# hihats.net
KiCad netlist of a schematic drawn in EAGLE
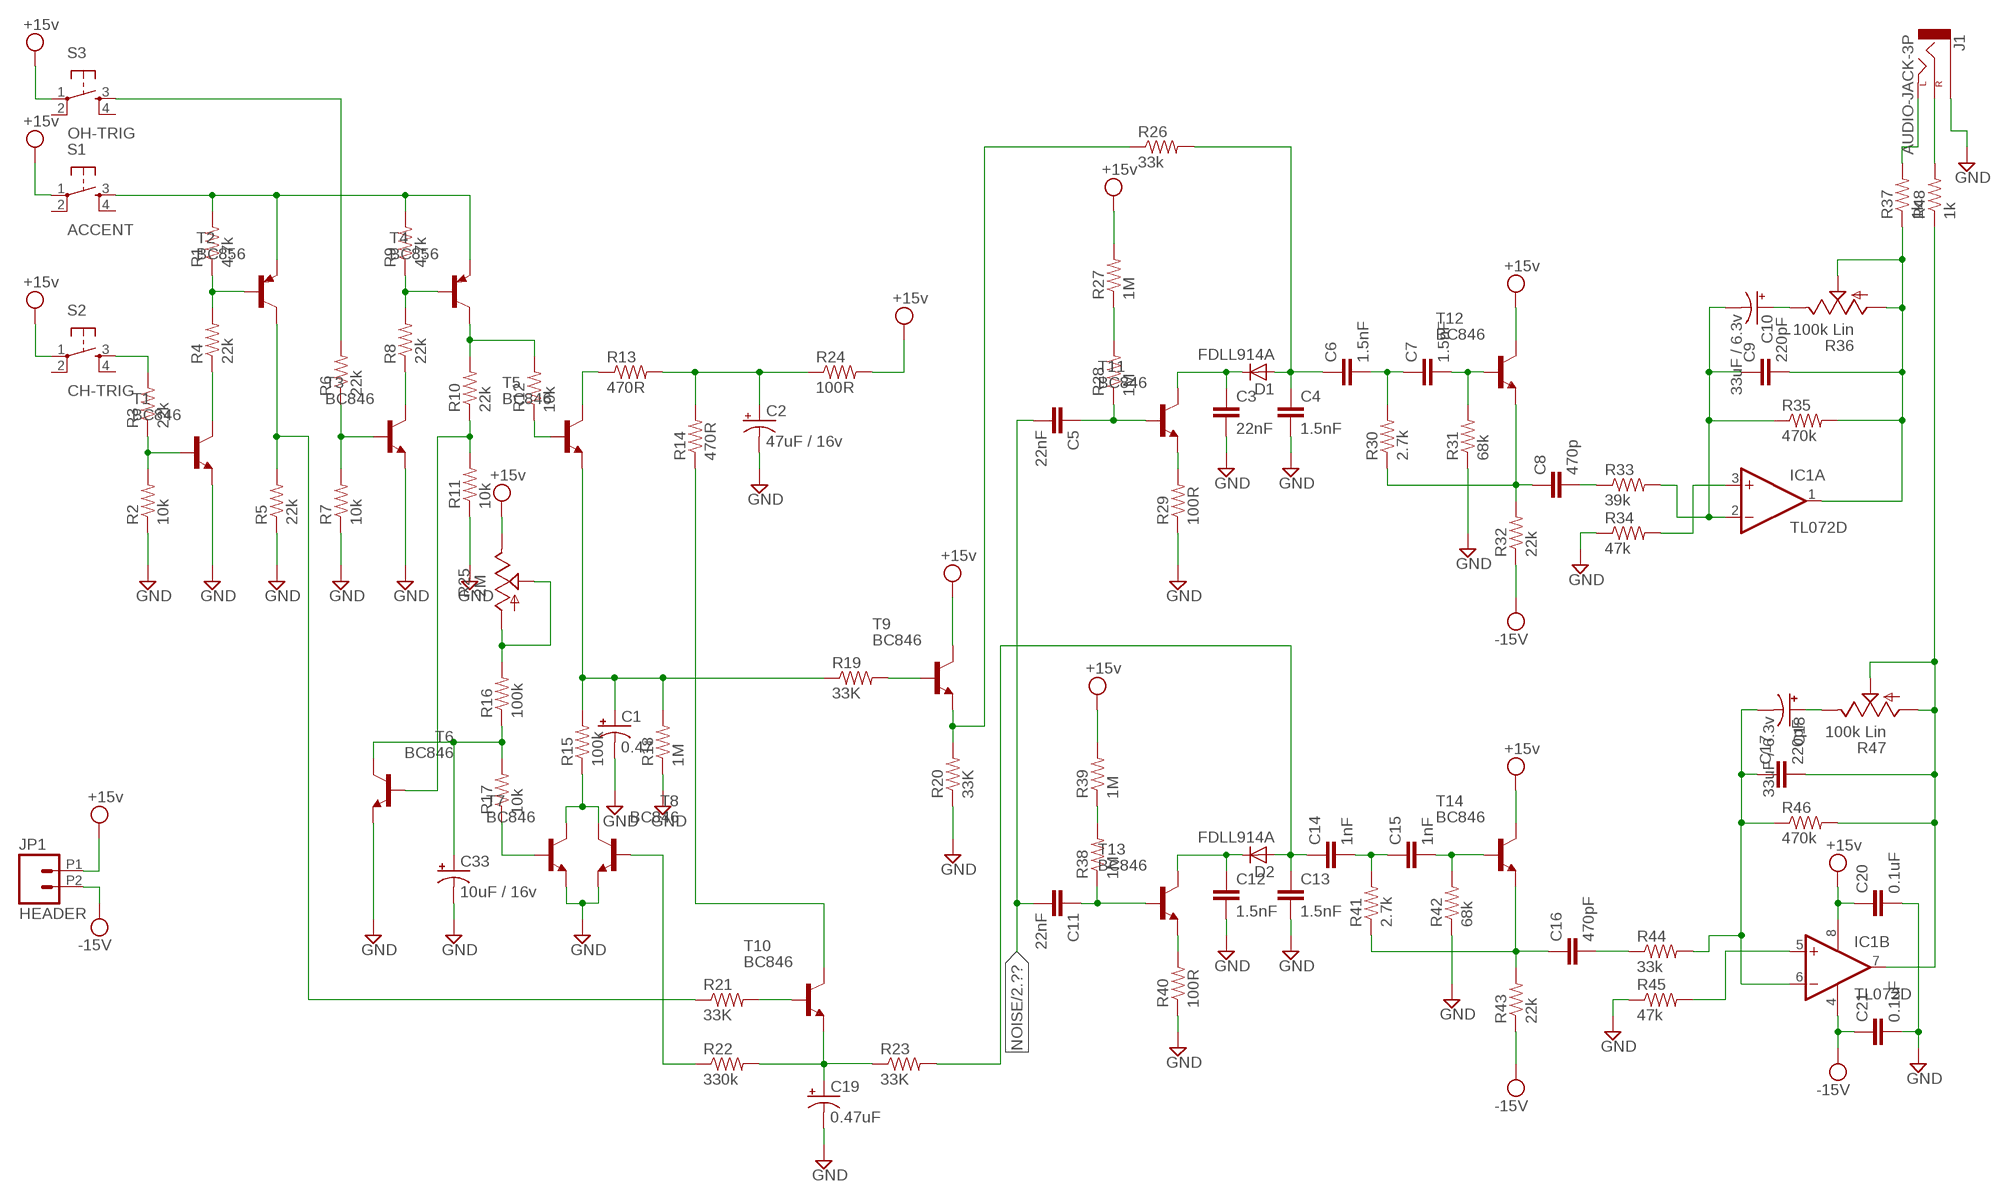
[diagram p0: schematic, sheet 1]
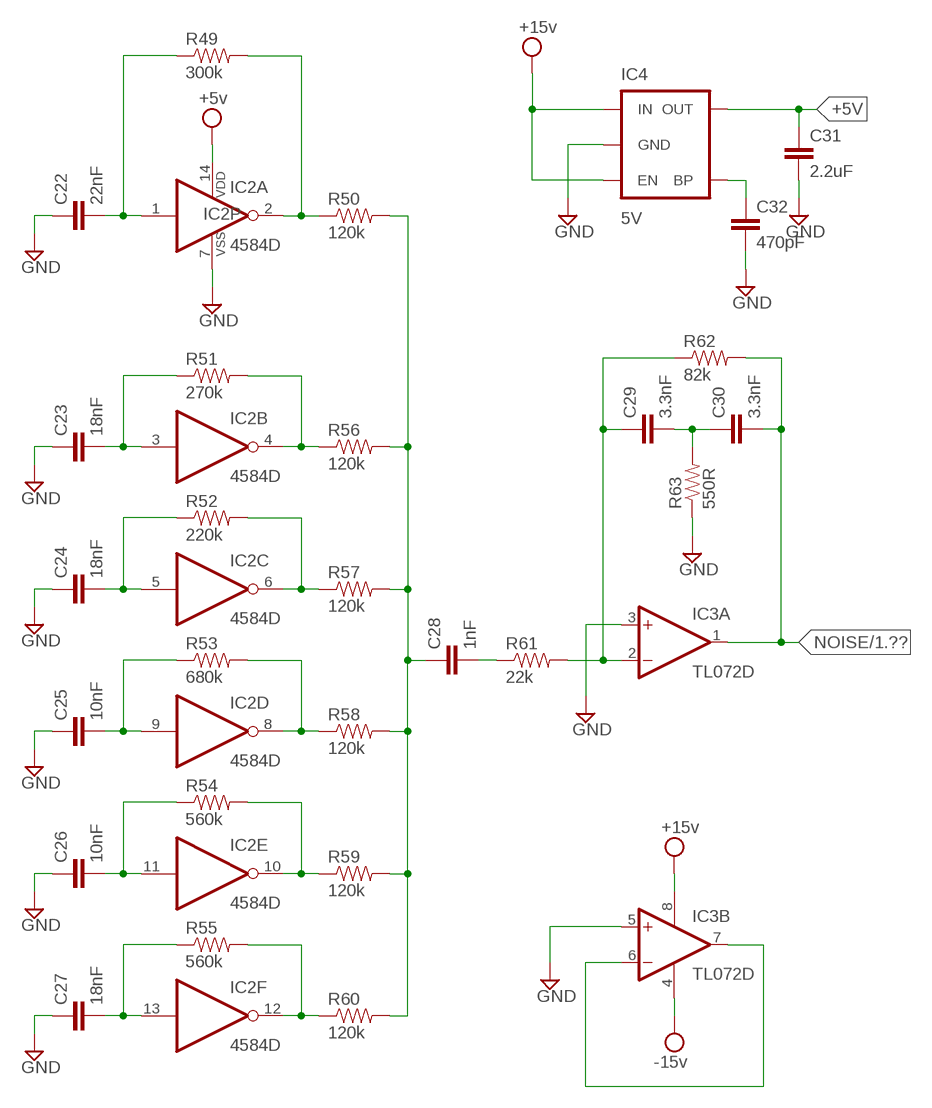
[diagram p1: schematic, sheet 2]

(export (version "E")
  (design (tool "Eeschema 10.0.6"))
  (components
    (comp (ref "C22")
      (value "22nF")
      (footprint "eagle-import:0805")
      (fields (field (name "PARTNO") "C0805C682K5RACTU"))
      (libsource (lib "eagle-import") (part "CAP0805"))
    )
    (comp (ref "C23")
      (value "18nF")
      (footprint "eagle-import:0805")
      (fields (field (name "PARTNO") "C0805C682K5RACTU"))
      (libsource (lib "eagle-import") (part "CAP0805"))
    )
    (comp (ref "C24")
      (value "18nF")
      (footprint "eagle-import:0805")
      (fields (field (name "PARTNO") "C0805C682K5RACTU"))
      (libsource (lib "eagle-import") (part "CAP0805"))
    )
    (comp (ref "C25")
      (value "10nF")
      (footprint "eagle-import:0805")
      (fields (field (name "PARTNO") "C0805C682K5RACTU"))
      (libsource (lib "eagle-import") (part "CAP0805"))
    )
    (comp (ref "C26")
      (value "10nF")
      (footprint "eagle-import:0805")
      (fields (field (name "PARTNO") "C0805C682K5RACTU"))
      (libsource (lib "eagle-import") (part "CAP0805"))
    )
    (comp (ref "C27")
      (value "18nF")
      (footprint "eagle-import:0805")
      (fields (field (name "PARTNO") "C0805C682K5RACTU"))
      (libsource (lib "eagle-import") (part "CAP0805"))
    )
    (comp (ref "C28")
      (value "1nF")
      (footprint "eagle-import:0805")
      (fields (field (name "PARTNO") "C0805C682K5RACTU"))
      (libsource (lib "eagle-import") (part "CAP0805"))
    )
    (comp (ref "C29")
      (value "3.3nF")
      (footprint "eagle-import:0805")
      (fields (field (name "PARTNO") "C0805C682K5RACTU"))
      (libsource (lib "eagle-import") (part "CAP0805"))
    )
    (comp (ref "C30")
      (value "3.3nF")
      (footprint "eagle-import:0805")
      (fields (field (name "PARTNO") "C0805C682K5RACTU"))
      (libsource (lib "eagle-import") (part "CAP0805"))
    )
    (comp (ref "C31")
      (value "2.2uF")
      (footprint "eagle-import:0805")
      (fields (field (name "PARTNO") "C0805C682K5RACTU"))
      (libsource (lib "eagle-import") (part "CAP0805"))
    )
    (comp (ref "C32")
      (value "470pF")
      (footprint "eagle-import:0805")
      (fields (field (name "PARTNO") "C0805C682K5RACTU"))
      (libsource (lib "eagle-import") (part "CAP0805"))
    )
    (comp (ref "IC2")
      (value "4584D")
      (footprint "eagle-import:SO14")
      (fields (field (name "PARTNO") "BU4584BF-E2"))
      (libsource (lib "eagle-import") (part "4584D"))
    )
    (comp (ref "IC3")
      (value "TL072D")
      (footprint "eagle-import:SO08")
      (fields (field (name "PARTNO") "TL072SG-13"))
      (libsource (lib "eagle-import") (part "TL072D"))
    )
    (comp (ref "IC4")
      (value "5V")
      (footprint "eagle-import:SOT23-5")
      (fields (field (name "PARTNO") "MIC5205-5.0YM5 TR"))
      (libsource (lib "eagle-import") (part "V_REG_MIC52055V"))
    )
    (comp (ref "R49")
      (value "300k")
      (footprint "eagle-import:0805")
      (fields (field (name "PARTNO") "RMCF0805FT10K0"))
      (libsource (lib "eagle-import") (part "RESISTOR0805-RES"))
    )
    (comp (ref "R50")
      (value "120k")
      (footprint "eagle-import:0805")
      (fields (field (name "PARTNO") "RMCF0805FT10K0"))
      (libsource (lib "eagle-import") (part "RESISTOR0805-RES"))
    )
    (comp (ref "R51")
      (value "270k")
      (footprint "eagle-import:0805")
      (fields (field (name "PARTNO") "RMCF0805FT10K0"))
      (libsource (lib "eagle-import") (part "RESISTOR0805-RES"))
    )
    (comp (ref "R52")
      (value "220k")
      (footprint "eagle-import:0805")
      (fields (field (name "PARTNO") "RMCF0805FT10K0"))
      (libsource (lib "eagle-import") (part "RESISTOR0805-RES"))
    )
    (comp (ref "R53")
      (value "680k")
      (footprint "eagle-import:0805")
      (fields (field (name "PARTNO") "RMCF0805FT10K0"))
      (libsource (lib "eagle-import") (part "RESISTOR0805-RES"))
    )
    (comp (ref "R54")
      (value "560k")
      (footprint "eagle-import:0805")
      (fields (field (name "PARTNO") "RMCF0805FT10K0"))
      (libsource (lib "eagle-import") (part "RESISTOR0805-RES"))
    )
    (comp (ref "R55")
      (value "560k")
      (footprint "eagle-import:0805")
      (fields (field (name "PARTNO") "RMCF0805FT10K0"))
      (libsource (lib "eagle-import") (part "RESISTOR0805-RES"))
    )
    (comp (ref "R56")
      (value "120k")
      (footprint "eagle-import:0805")
      (fields (field (name "PARTNO") "RMCF0805FT10K0"))
      (libsource (lib "eagle-import") (part "RESISTOR0805-RES"))
    )
    (comp (ref "R57")
      (value "120k")
      (footprint "eagle-import:0805")
      (fields (field (name "PARTNO") "RMCF0805FT10K0"))
      (libsource (lib "eagle-import") (part "RESISTOR0805-RES"))
    )
    (comp (ref "R58")
      (value "120k")
      (footprint "eagle-import:0805")
      (fields (field (name "PARTNO") "RMCF0805FT10K0"))
      (libsource (lib "eagle-import") (part "RESISTOR0805-RES"))
    )
    (comp (ref "R59")
      (value "120k")
      (footprint "eagle-import:0805")
      (fields (field (name "PARTNO") "RMCF0805FT10K0"))
      (libsource (lib "eagle-import") (part "RESISTOR0805-RES"))
    )
    (comp (ref "R60")
      (value "120k")
      (footprint "eagle-import:0805")
      (fields (field (name "PARTNO") "RMCF0805FT10K0"))
      (libsource (lib "eagle-import") (part "RESISTOR0805-RES"))
    )
    (comp (ref "R61")
      (value "22k")
      (footprint "eagle-import:0805")
      (fields (field (name "PARTNO") "RMCF0805FT10K0"))
      (libsource (lib "eagle-import") (part "RESISTOR0805-RES"))
    )
    (comp (ref "R62")
      (value "82k")
      (footprint "eagle-import:0805")
      (fields (field (name "PARTNO") "RMCF0805FT10K0"))
      (libsource (lib "eagle-import") (part "RESISTOR0805-RES"))
    )
    (comp (ref "R63")
      (value "550R")
      (footprint "eagle-import:0805")
      (fields (field (name "PARTNO") "RMCF0805FT10K0"))
      (libsource (lib "eagle-import") (part "RESISTOR0805-RES"))
    )
    (comp (ref "C1")
      (value "0.47")
      (footprint "eagle-import:PANASONIC_VS_B-2")
      (fields (field (name "PARTNO") "EEE-1HAR47AR"))
      (libsource (lib "eagle-import") (part "CAP-POLPANASONIC_B-2"))
    )
    (comp (ref "C2")
      (value "47uF / 16v")
      (footprint "eagle-import:PANASONIC_VS_B-2")
      (fields (field (name "PARTNO") "EEE-1CA470WR"))
      (libsource (lib "eagle-import") (part "CAP-POLPANASONIC_B-2"))
    )
    (comp (ref "C3")
      (value "22nF")
      (footprint "eagle-import:0805")
      (fields (field (name "PARTNO") "C0805C682K5RACTU"))
      (libsource (lib "eagle-import") (part "CAP0805"))
    )
    (comp (ref "C4")
      (value "1.5nF")
      (footprint "eagle-import:0805")
      (fields (field (name "PARTNO") "C0805C682K5RACTU"))
      (libsource (lib "eagle-import") (part "CAP0805"))
    )
    (comp (ref "C5")
      (value "22nF")
      (footprint "eagle-import:0805")
      (fields (field (name "PARTNO") "C0805C682K5RACTU"))
      (libsource (lib "eagle-import") (part "CAP0805"))
    )
    (comp (ref "C6")
      (value "1.5nF")
      (footprint "eagle-import:0805")
      (fields (field (name "PARTNO") "C0805C682K5RACTU"))
      (libsource (lib "eagle-import") (part "CAP0805"))
    )
    (comp (ref "C7")
      (value "1.5nF")
      (footprint "eagle-import:0805")
      (fields (field (name "PARTNO") "C0805C682K5RACTU"))
      (libsource (lib "eagle-import") (part "CAP0805"))
    )
    (comp (ref "C8")
      (value "470p")
      (footprint "eagle-import:0805")
      (fields (field (name "PARTNO") "C0805C682K5RACTU"))
      (libsource (lib "eagle-import") (part "CAP0805"))
    )
    (comp (ref "C9")
      (value "220pF")
      (footprint "eagle-import:0805")
      (fields (field (name "PARTNO") "C0805C682K5RACTU"))
      (libsource (lib "eagle-import") (part "CAP0805"))
    )
    (comp (ref "C10")
      (value "33uF / 6.3v")
      (footprint "eagle-import:PANASONIC_VS_B-2")
      (fields (field (name "PARTNO") "EEE-1AA330WAR"))
      (libsource (lib "eagle-import") (part "CAP-POLPANASONIC_B-2"))
    )
    (comp (ref "C11")
      (value "22nF")
      (footprint "eagle-import:0805")
      (fields (field (name "PARTNO") "C0805C682K5RACTU"))
      (libsource (lib "eagle-import") (part "CAP0805"))
    )
    (comp (ref "C12")
      (value "1.5nF")
      (footprint "eagle-import:0805")
      (fields (field (name "PARTNO") "C0805C682K5RACTU"))
      (libsource (lib "eagle-import") (part "CAP0805"))
    )
    (comp (ref "C13")
      (value "1.5nF")
      (footprint "eagle-import:0805")
      (fields (field (name "PARTNO") "C0805C682K5RACTU"))
      (libsource (lib "eagle-import") (part "CAP0805"))
    )
    (comp (ref "C14")
      (value "1nF")
      (footprint "eagle-import:0805")
      (fields (field (name "PARTNO") "C0805C682K5RACTU"))
      (libsource (lib "eagle-import") (part "CAP0805"))
    )
    (comp (ref "C15")
      (value "1nF")
      (footprint "eagle-import:0805")
      (fields (field (name "PARTNO") "C0805C682K5RACTU"))
      (libsource (lib "eagle-import") (part "CAP0805"))
    )
    (comp (ref "C16")
      (value "470pF")
      (footprint "eagle-import:0805")
      (fields (field (name "PARTNO") "C0805C682K5RACTU"))
      (libsource (lib "eagle-import") (part "CAP0805"))
    )
    (comp (ref "C17")
      (value "220pF")
      (footprint "eagle-import:0805")
      (fields (field (name "PARTNO") "C0805C682K5RACTU"))
      (libsource (lib "eagle-import") (part "CAP0805"))
    )
    (comp (ref "C18")
      (value "33uF / 6.3v")
      (footprint "eagle-import:PANASONIC_VS_B-2")
      (fields (field (name "PARTNO") "EEE-1AA330WAR"))
      (libsource (lib "eagle-import") (part "CAP-POLPANASONIC_B-2"))
    )
    (comp (ref "C19")
      (value "0.47uF")
      (footprint "eagle-import:PANASONIC_VS_B-2")
      (fields (field (name "PARTNO") "UWJ1HR47MCL1GB"))
      (libsource (lib "eagle-import") (part "CAP-POLPANASONIC_B-2"))
    )
    (comp (ref "C20")
      (value "0.1uF")
      (footprint "eagle-import:0805")
      (fields (field (name "PARTNO") "C0805C682K5RACTU"))
      (libsource (lib "eagle-import") (part "CAP0805"))
    )
    (comp (ref "C21")
      (value "0.1uF")
      (footprint "eagle-import:0805")
      (fields (field (name "PARTNO") "C0805C682K5RACTU"))
      (libsource (lib "eagle-import") (part "CAP0805"))
    )
    (comp (ref "C33")
      (value "10uF / 16v")
      (footprint "eagle-import:PANASONIC_VS_B-2")
      (fields (field (name "PARTNO") "EEE-1VA100WAR"))
      (libsource (lib "eagle-import") (part "CAP-POLPANASONIC_B-2"))
    )
    (comp (ref "D1")
      (value "FDLL914A")
      (footprint "eagle-import:MELF-MLL34")
      (libsource (lib "eagle-import") (part "D-MLL-34"))
    )
    (comp (ref "D2")
      (value "FDLL914A")
      (footprint "eagle-import:MELF-MLL34")
      (libsource (lib "eagle-import") (part "D-MLL-34"))
    )
    (comp (ref "IC1")
      (value "TL072D")
      (footprint "eagle-import:SO08")
      (fields (field (name "PARTNO") "TL072SG-13"))
      (libsource (lib "eagle-import") (part "TL072D"))
    )
    (comp (ref "J1")
      (value "AUDIO-JACK-3P")
      (footprint "eagle-import:CUI-352X-SMT")
      (fields (field (name "PARTNO") "SJ-3523-SMT-TR"))
      (libsource (lib "eagle-import") (part "AUDIO-JACK-3P"))
    )
    (comp (ref "JP1")
      (value "HEADER")
      (footprint "eagle-import:1X02-5.08-SCREWTERM")
      (libsource (lib "eagle-import") (part "HEADER"))
    )
    (comp (ref "R1")
      (value "4.7k")
      (footprint "eagle-import:0805")
      (fields (field (name "PARTNO") "RMCF0805FT10K0"))
      (libsource (lib "eagle-import") (part "RESISTOR0805-RES"))
    )
    (comp (ref "R2")
      (value "10k")
      (footprint "eagle-import:0805")
      (fields (field (name "PARTNO") "RMCF0805FT10K0"))
      (libsource (lib "eagle-import") (part "RESISTOR0805-RES"))
    )
    (comp (ref "R3")
      (value "22k")
      (footprint "eagle-import:0805")
      (fields (field (name "PARTNO") "RMCF0805FT10K0"))
      (libsource (lib "eagle-import") (part "RESISTOR0805-RES"))
    )
    (comp (ref "R4")
      (value "22k")
      (footprint "eagle-import:0805")
      (fields (field (name "PARTNO") "RMCF0805FT10K0"))
      (libsource (lib "eagle-import") (part "RESISTOR0805-RES"))
    )
    (comp (ref "R5")
      (value "22k")
      (footprint "eagle-import:0805")
      (fields (field (name "PARTNO") "RMCF0805FT10K0"))
      (libsource (lib "eagle-import") (part "RESISTOR0805-RES"))
    )
    (comp (ref "R6")
      (value "22k")
      (footprint "eagle-import:0805")
      (fields (field (name "PARTNO") "RMCF0805FT10K0"))
      (libsource (lib "eagle-import") (part "RESISTOR0805-RES"))
    )
    (comp (ref "R7")
      (value "10k")
      (footprint "eagle-import:0805")
      (fields (field (name "PARTNO") "RMCF0805FT10K0"))
      (libsource (lib "eagle-import") (part "RESISTOR0805-RES"))
    )
    (comp (ref "R8")
      (value "22k")
      (footprint "eagle-import:0805")
      (fields (field (name "PARTNO") "RMCF0805FT10K0"))
      (libsource (lib "eagle-import") (part "RESISTOR0805-RES"))
    )
    (comp (ref "R9")
      (value "4.7k")
      (footprint "eagle-import:0805")
      (fields (field (name "PARTNO") "RMCF0805FT10K0"))
      (libsource (lib "eagle-import") (part "RESISTOR0805-RES"))
    )
    (comp (ref "R10")
      (value "22k")
      (footprint "eagle-import:0805")
      (fields (field (name "PARTNO") "RMCF0805FT10K0"))
      (libsource (lib "eagle-import") (part "RESISTOR0805-RES"))
    )
    (comp (ref "R11")
      (value "10k")
      (footprint "eagle-import:0805")
      (fields (field (name "PARTNO") "RMCF0805FT10K0"))
      (libsource (lib "eagle-import") (part "RESISTOR0805-RES"))
    )
    (comp (ref "R12")
      (value "10k")
      (footprint "eagle-import:0805")
      (fields (field (name "PARTNO") "RMCF0805FT10K0"))
      (libsource (lib "eagle-import") (part "RESISTOR0805-RES"))
    )
    (comp (ref "R13")
      (value "470R")
      (footprint "eagle-import:0805")
      (fields (field (name "PARTNO") "RMCF0805FT10K0"))
      (libsource (lib "eagle-import") (part "RESISTOR0805-RES"))
    )
    (comp (ref "R14")
      (value "470R")
      (footprint "eagle-import:0805")
      (fields (field (name "PARTNO") "RMCF0805FT10K0"))
      (libsource (lib "eagle-import") (part "RESISTOR0805-RES"))
    )
    (comp (ref "R15")
      (value "100k")
      (footprint "eagle-import:0805")
      (fields (field (name "PARTNO") "RMCF0805FT10K0"))
      (libsource (lib "eagle-import") (part "RESISTOR0805-RES"))
    )
    (comp (ref "R16")
      (value "100k")
      (footprint "eagle-import:0805")
      (fields (field (name "PARTNO") "RMCF0805FT10K0"))
      (libsource (lib "eagle-import") (part "RESISTOR0805-RES"))
    )
    (comp (ref "R17")
      (value "10k")
      (footprint "eagle-import:0805")
      (fields (field (name "PARTNO") "RMCF0805FT10K0"))
      (libsource (lib "eagle-import") (part "RESISTOR0805-RES"))
    )
    (comp (ref "R18")
      (value "1M")
      (footprint "eagle-import:0805")
      (fields (field (name "PARTNO") "RMCF0805FT10K0"))
      (libsource (lib "eagle-import") (part "RESISTOR0805-RES"))
    )
    (comp (ref "R19")
      (value "33K")
      (footprint "eagle-import:0805")
      (fields (field (name "PARTNO") "RMCF0805FT10K0"))
      (libsource (lib "eagle-import") (part "RESISTOR0805-RES"))
    )
    (comp (ref "R20")
      (value "33K")
      (footprint "eagle-import:0805")
      (fields (field (name "PARTNO") "RMCF0805FT10K0"))
      (libsource (lib "eagle-import") (part "RESISTOR0805-RES"))
    )
    (comp (ref "R21")
      (value "33K")
      (footprint "eagle-import:0805")
      (fields (field (name "PARTNO") "RMCF0805FT10K0"))
      (libsource (lib "eagle-import") (part "RESISTOR0805-RES"))
    )
    (comp (ref "R22")
      (value "330k")
      (footprint "eagle-import:0805")
      (fields (field (name "PARTNO") "RMCF0805FT10K0"))
      (libsource (lib "eagle-import") (part "RESISTOR0805-RES"))
    )
    (comp (ref "R23")
      (value "33K")
      (footprint "eagle-import:0805")
      (fields (field (name "PARTNO") "RMCF0805FT10K0"))
      (libsource (lib "eagle-import") (part "RESISTOR0805-RES"))
    )
    (comp (ref "R24")
      (value "100R")
      (footprint "eagle-import:0805")
      (fields (field (name "PARTNO") "RMCF0805FT10K0"))
      (libsource (lib "eagle-import") (part "RESISTOR0805-RES"))
    )
    (comp (ref "R25")
      (value "2M")
      (footprint "eagle-import:POTENTIOMETER-3352P")
      (fields (field (name "PARTNO") "3352P-1-205LF"))
      (libsource (lib "eagle-import") (part "POTTHUMB-3352"))
    )
    (comp (ref "R26")
      (value "33k")
      (footprint "eagle-import:0805")
      (fields (field (name "PARTNO") "RMCF0805FT10K0"))
      (libsource (lib "eagle-import") (part "RESISTOR0805-RES"))
    )
    (comp (ref "R27")
      (value "1M")
      (footprint "eagle-import:0805")
      (fields (field (name "PARTNO") "RMCF0805FT10K0"))
      (libsource (lib "eagle-import") (part "RESISTOR0805-RES"))
    )
    (comp (ref "R28")
      (value "1M")
      (footprint "eagle-import:0805")
      (fields (field (name "PARTNO") "RMCF0805FT10K0"))
      (libsource (lib "eagle-import") (part "RESISTOR0805-RES"))
    )
    (comp (ref "R29")
      (value "100R")
      (footprint "eagle-import:0805")
      (fields (field (name "PARTNO") "RMCF0805FT10K0"))
      (libsource (lib "eagle-import") (part "RESISTOR0805-RES"))
    )
    (comp (ref "R30")
      (value "2.7k")
      (footprint "eagle-import:0805")
      (fields (field (name "PARTNO") "RMCF0805FT10K0"))
      (libsource (lib "eagle-import") (part "RESISTOR0805-RES"))
    )
    (comp (ref "R31")
      (value "68k")
      (footprint "eagle-import:0805")
      (fields (field (name "PARTNO") "RMCF0805FT10K0"))
      (libsource (lib "eagle-import") (part "RESISTOR0805-RES"))
    )
    (comp (ref "R32")
      (value "22k")
      (footprint "eagle-import:0805")
      (fields (field (name "PARTNO") "RMCF0805FT10K0"))
      (libsource (lib "eagle-import") (part "RESISTOR0805-RES"))
    )
    (comp (ref "R33")
      (value "39k")
      (footprint "eagle-import:0805")
      (fields (field (name "PARTNO") "RMCF0805FT10K0"))
      (libsource (lib "eagle-import") (part "RESISTOR0805-RES"))
    )
    (comp (ref "R34")
      (value "47k")
      (footprint "eagle-import:0805")
      (fields (field (name "PARTNO") "RMCF0805FT10K0"))
      (libsource (lib "eagle-import") (part "RESISTOR0805-RES"))
    )
    (comp (ref "R35")
      (value "470k")
      (footprint "eagle-import:0805")
      (fields (field (name "PARTNO") "RMCF0805FT10K0"))
      (libsource (lib "eagle-import") (part "RESISTOR0805-RES"))
    )
    (comp (ref "R36")
      (value "100k Lin")
      (footprint "eagle-import:POTENTIOMETER-CTS296")
      (fields (field (name "PARTNO") "296UD104B1N"))
      (libsource (lib "eagle-import") (part "POTCTS296"))
    )
    (comp (ref "R37")
      (value "1k")
      (footprint "eagle-import:0805")
      (fields (field (name "PARTNO") "RMCF0805FT10K0"))
      (libsource (lib "eagle-import") (part "RESISTOR0805-RES"))
    )
    (comp (ref "R38")
      (value "1M")
      (footprint "eagle-import:0805")
      (fields (field (name "PARTNO") "RMCF0805FT10K0"))
      (libsource (lib "eagle-import") (part "RESISTOR0805-RES"))
    )
    (comp (ref "R39")
      (value "1M")
      (footprint "eagle-import:0805")
      (fields (field (name "PARTNO") "RMCF0805FT10K0"))
      (libsource (lib "eagle-import") (part "RESISTOR0805-RES"))
    )
    (comp (ref "R40")
      (value "100R")
      (footprint "eagle-import:0805")
      (fields (field (name "PARTNO") "RMCF0805FT10K0"))
      (libsource (lib "eagle-import") (part "RESISTOR0805-RES"))
    )
    (comp (ref "R41")
      (value "2.7k")
      (footprint "eagle-import:0805")
      (fields (field (name "PARTNO") "RMCF0805FT10K0"))
      (libsource (lib "eagle-import") (part "RESISTOR0805-RES"))
    )
    (comp (ref "R42")
      (value "68k")
      (footprint "eagle-import:0805")
      (fields (field (name "PARTNO") "RMCF0805FT10K0"))
      (libsource (lib "eagle-import") (part "RESISTOR0805-RES"))
    )
    (comp (ref "R43")
      (value "22k")
      (footprint "eagle-import:0805")
      (fields (field (name "PARTNO") "RMCF0805FT10K0"))
      (libsource (lib "eagle-import") (part "RESISTOR0805-RES"))
    )
    (comp (ref "R44")
      (value "33k")
      (footprint "eagle-import:0805")
      (fields (field (name "PARTNO") "RMCF0805FT10K0"))
      (libsource (lib "eagle-import") (part "RESISTOR0805-RES"))
    )
    (comp (ref "R45")
      (value "47k")
      (footprint "eagle-import:0805")
      (fields (field (name "PARTNO") "RMCF0805FT10K0"))
      (libsource (lib "eagle-import") (part "RESISTOR0805-RES"))
    )
    (comp (ref "R46")
      (value "470k")
      (footprint "eagle-import:0805")
      (fields (field (name "PARTNO") "RMCF0805FT10K0"))
      (libsource (lib "eagle-import") (part "RESISTOR0805-RES"))
    )
    (comp (ref "R47")
      (value "100k Lin")
      (footprint "eagle-import:POTENTIOMETER-CTS296")
      (fields (field (name "PARTNO") "296UD104B1N"))
      (libsource (lib "eagle-import") (part "POTCTS296"))
    )
    (comp (ref "R48")
      (value "1k")
      (footprint "eagle-import:0805")
      (fields (field (name "PARTNO") "RMCF0805FT10K0"))
      (libsource (lib "eagle-import") (part "RESISTOR0805-RES"))
    )
    (comp (ref "S1")
      (value "ACCENT")
      (footprint "eagle-import:TACTILE_SWITCH_SMD")
      (fields (field (name "PARTNO") "PTS525SM10SMTR LFS"))
      (libsource (lib "eagle-import") (part "TAC_SWITCHSMD"))
    )
    (comp (ref "S2")
      (value "CH-TRIG")
      (footprint "eagle-import:TACTILE_SWITCH_SMD")
      (fields (field (name "PARTNO") "PTS525SM10SMTR LFS"))
      (libsource (lib "eagle-import") (part "TAC_SWITCHSMD"))
    )
    (comp (ref "S3")
      (value "OH-TRIG")
      (footprint "eagle-import:TACTILE_SWITCH_SMD")
      (fields (field (name "PARTNO") "PTS525SM10SMTR LFS"))
      (libsource (lib "eagle-import") (part "TAC_SWITCHSMD"))
    )
    (comp (ref "T1")
      (value "BC846")
      (footprint "eagle-import:SOT23")
      (fields (field (name "PARTNO") "BC846BMTF"))
      (libsource (lib "eagle-import") (part "BC846"))
    )
    (comp (ref "T2")
      (value "BC856")
      (footprint "eagle-import:SOT23-BEC")
      (fields (field (name "PARTNO") "BC856BMTF"))
      (libsource (lib "eagle-import") (part "-PNP-SOT23-BECBC856B"))
    )
    (comp (ref "T3")
      (value "BC846")
      (footprint "eagle-import:SOT23")
      (fields (field (name "PARTNO") "BC846BMTF"))
      (libsource (lib "eagle-import") (part "BC846"))
    )
    (comp (ref "T4")
      (value "BC856")
      (footprint "eagle-import:SOT23-BEC")
      (fields (field (name "PARTNO") "BC856BMTF"))
      (libsource (lib "eagle-import") (part "-PNP-SOT23-BECBC856B"))
    )
    (comp (ref "T5")
      (value "BC846")
      (footprint "eagle-import:SOT23")
      (fields (field (name "PARTNO") "BC846BMTF"))
      (libsource (lib "eagle-import") (part "BC846"))
    )
    (comp (ref "T6")
      (value "BC846")
      (footprint "eagle-import:SOT23")
      (fields (field (name "PARTNO") "BC846BMTF"))
      (libsource (lib "eagle-import") (part "BC846"))
    )
    (comp (ref "T7")
      (value "BC846")
      (footprint "eagle-import:SOT23")
      (fields (field (name "PARTNO") "BC846BMTF"))
      (libsource (lib "eagle-import") (part "BC846"))
    )
    (comp (ref "T8")
      (value "BC846")
      (footprint "eagle-import:SOT23")
      (fields (field (name "PARTNO") "BC846BMTF"))
      (libsource (lib "eagle-import") (part "BC846"))
    )
    (comp (ref "T9")
      (value "BC846")
      (footprint "eagle-import:SOT23")
      (fields (field (name "PARTNO") "BC846BMTF"))
      (libsource (lib "eagle-import") (part "BC846"))
    )
    (comp (ref "T10")
      (value "BC846")
      (footprint "eagle-import:SOT23")
      (fields (field (name "PARTNO") "BC846BMTF"))
      (libsource (lib "eagle-import") (part "BC846"))
    )
    (comp (ref "T11")
      (value "BC846")
      (footprint "eagle-import:SOT23")
      (fields (field (name "PARTNO") "BC846BMTF"))
      (libsource (lib "eagle-import") (part "BC846"))
    )
    (comp (ref "T12")
      (value "BC846")
      (footprint "eagle-import:SOT23")
      (fields (field (name "PARTNO") "BC846BMTF"))
      (libsource (lib "eagle-import") (part "BC846"))
    )
    (comp (ref "T13")
      (value "BC846")
      (footprint "eagle-import:SOT23")
      (fields (field (name "PARTNO") "BC846BMTF"))
      (libsource (lib "eagle-import") (part "BC846"))
    )
    (comp (ref "T14")
      (value "BC846")
      (footprint "eagle-import:SOT23")
      (fields (field (name "PARTNO") "BC846BMTF"))
      (libsource (lib "eagle-import") (part "BC846"))
    )
  )
  (nets
    (net (code "1") (name "+5V") (class "Default")
      (node (ref "C31") (pin "1") (pinfunction "1_1") (pintype "passive"))
      (node (ref "IC2") (pin "14") (pinfunction "VDD_14") (pintype "power_in"))
      (node (ref "IC4") (pin "5") (pinfunction "OUT_5") (pintype "passive"))
    )
    (net (code "2") (name "+15V") (class "Default")
      (node (ref "C20") (pin "1") (pinfunction "1_1") (pintype "passive"))
      (node (ref "IC1") (pin "8") (pinfunction "V+_8") (pintype "power_in"))
      (node (ref "IC3") (pin "8") (pinfunction "V+_8") (pintype "power_in"))
      (node (ref "IC4") (pin "1") (pinfunction "IN_1") (pintype "input"))
      (node (ref "IC4") (pin "3") (pinfunction "EN_3") (pintype "input"))
      (node (ref "JP1") (pin "P1") (pinfunction "2_P1") (pintype "passive"))
      (node (ref "R24") (pin "2") (pinfunction "2_2") (pintype "passive"))
      (node (ref "R25") (pin "P$3") (pinfunction "E_P$3") (pintype "passive"))
      (node (ref "R27") (pin "2") (pinfunction "2_2") (pintype "passive"))
      (node (ref "R39") (pin "2") (pinfunction "2_2") (pintype "passive"))
      (node (ref "S1") (pin "1") (pinfunction "1_1") (pintype "passive"))
      (node (ref "S2") (pin "1") (pinfunction "1_1") (pintype "passive"))
      (node (ref "S3") (pin "1") (pinfunction "1_1") (pintype "passive"))
      (node (ref "T12") (pin "3") (pinfunction "C_3") (pintype "passive"))
      (node (ref "T14") (pin "3") (pinfunction "C_3") (pintype "passive"))
      (node (ref "T9") (pin "3") (pinfunction "C_3") (pintype "passive"))
    )
    (net (code "3") (name "-15V") (class "Default")
      (node (ref "C21") (pin "1") (pinfunction "1_1") (pintype "passive"))
      (node (ref "IC1") (pin "4") (pinfunction "V-_4") (pintype "power_in"))
      (node (ref "IC3") (pin "4") (pinfunction "V-_4") (pintype "power_in"))
      (node (ref "JP1") (pin "P2") (pinfunction "1_P2") (pintype "passive"))
      (node (ref "R32") (pin "1") (pinfunction "1_1") (pintype "passive"))
      (node (ref "R43") (pin "1") (pinfunction "1_1") (pintype "passive"))
    )
    (net (code "4") (name "GND") (class "Default")
      (node (ref "C1") (pin "-") (pinfunction "-_-") (pintype "passive"))
      (node (ref "C12") (pin "2") (pinfunction "2_2") (pintype "passive"))
      (node (ref "C13") (pin "2") (pinfunction "2_2") (pintype "passive"))
      (node (ref "C19") (pin "-") (pinfunction "-_-") (pintype "passive"))
      (node (ref "C2") (pin "-") (pinfunction "-_-") (pintype "passive"))
      (node (ref "C20") (pin "2") (pinfunction "2_2") (pintype "passive"))
      (node (ref "C21") (pin "2") (pinfunction "2_2") (pintype "passive"))
      (node (ref "C22") (pin "1") (pinfunction "1_1") (pintype "passive"))
      (node (ref "C23") (pin "1") (pinfunction "1_1") (pintype "passive"))
      (node (ref "C24") (pin "1") (pinfunction "1_1") (pintype "passive"))
      (node (ref "C25") (pin "1") (pinfunction "1_1") (pintype "passive"))
      (node (ref "C26") (pin "1") (pinfunction "1_1") (pintype "passive"))
      (node (ref "C27") (pin "1") (pinfunction "1_1") (pintype "passive"))
      (node (ref "C3") (pin "2") (pinfunction "2_2") (pintype "passive"))
      (node (ref "C31") (pin "2") (pinfunction "2_2") (pintype "passive"))
      (node (ref "C32") (pin "2") (pinfunction "2_2") (pintype "passive"))
      (node (ref "C33") (pin "-") (pinfunction "-_-") (pintype "passive"))
      (node (ref "C4") (pin "2") (pinfunction "2_2") (pintype "passive"))
      (node (ref "IC2") (pin "7") (pinfunction "VSS_7") (pintype "power_in"))
      (node (ref "IC3") (pin "3") (pinfunction "+IN_3") (pintype "input"))
      (node (ref "IC3") (pin "5") (pinfunction "+IN_5") (pintype "input"))
      (node (ref "IC4") (pin "2") (pinfunction "GND_2") (pintype "input"))
      (node (ref "J1") (pin "1") (pinfunction "SLEEVE_1") (pintype "bidirectional"))
      (node (ref "R11") (pin "1") (pinfunction "1_1") (pintype "passive"))
      (node (ref "R18") (pin "1") (pinfunction "1_1") (pintype "passive"))
      (node (ref "R2") (pin "1") (pinfunction "1_1") (pintype "passive"))
      (node (ref "R20") (pin "1") (pinfunction "1_1") (pintype "passive"))
      (node (ref "R29") (pin "1") (pinfunction "1_1") (pintype "passive"))
      (node (ref "R31") (pin "1") (pinfunction "1_1") (pintype "passive"))
      (node (ref "R34") (pin "1") (pinfunction "1_1") (pintype "passive"))
      (node (ref "R40") (pin "1") (pinfunction "1_1") (pintype "passive"))
      (node (ref "R42") (pin "1") (pinfunction "1_1") (pintype "passive"))
      (node (ref "R45") (pin "1") (pinfunction "1_1") (pintype "passive"))
      (node (ref "R5") (pin "1") (pinfunction "1_1") (pintype "passive"))
      (node (ref "R63") (pin "1") (pinfunction "1_1") (pintype "passive"))
      (node (ref "R7") (pin "1") (pinfunction "1_1") (pintype "passive"))
      (node (ref "T1") (pin "2") (pinfunction "E_2") (pintype "passive"))
      (node (ref "T3") (pin "2") (pinfunction "E_2") (pintype "passive"))
      (node (ref "T6") (pin "2") (pinfunction "E_2") (pintype "passive"))
      (node (ref "T7") (pin "2") (pinfunction "E_2") (pintype "passive"))
      (node (ref "T8") (pin "2") (pinfunction "E_2") (pintype "passive"))
    )
    (net (code "5") (name "NOISE") (class "Default")
      (node (ref "C11") (pin "2") (pinfunction "2_2") (pintype "passive"))
      (node (ref "C30") (pin "2") (pinfunction "2_2") (pintype "passive"))
      (node (ref "C5") (pin "2") (pinfunction "2_2") (pintype "passive"))
      (node (ref "IC3") (pin "1") (pinfunction "OUT_1") (pintype "output"))
      (node (ref "R62") (pin "2") (pinfunction "2_2") (pintype "passive"))
    )
    (net (code "6") (name "Net-(C2-Pad+)") (class "Default")
      (node (ref "C2") (pin "+") (pinfunction "+_+") (pintype "passive"))
      (node (ref "R13") (pin "2") (pinfunction "2_2") (pintype "passive"))
      (node (ref "R14") (pin "2") (pinfunction "2_2") (pintype "passive"))
      (node (ref "R24") (pin "1") (pinfunction "1_1") (pintype "passive"))
    )
    (net (code "7") (name "Net-(C6-Pad2)") (class "Default")
      (node (ref "C6") (pin "2") (pinfunction "2_2") (pintype "passive"))
      (node (ref "C7") (pin "1") (pinfunction "1_1") (pintype "passive"))
      (node (ref "R30") (pin "2") (pinfunction "2_2") (pintype "passive"))
    )
    (net (code "8") (name "Net-(C8-Pad2)") (class "Default")
      (node (ref "C8") (pin "2") (pinfunction "2_2") (pintype "passive"))
      (node (ref "R33") (pin "1") (pinfunction "1_1") (pintype "passive"))
    )
    (net (code "9") (name "Net-(C14-Pad2)") (class "Default")
      (node (ref "C14") (pin "2") (pinfunction "2_2") (pintype "passive"))
      (node (ref "C15") (pin "1") (pinfunction "1_1") (pintype "passive"))
      (node (ref "R41") (pin "2") (pinfunction "2_2") (pintype "passive"))
    )
    (net (code "10") (name "Net-(C16-Pad2)") (class "Default")
      (node (ref "C16") (pin "2") (pinfunction "2_2") (pintype "passive"))
      (node (ref "R44") (pin "1") (pinfunction "1_1") (pintype "passive"))
    )
    (net (code "11") (name "Net-(C28-Pad1)") (class "Default")
      (node (ref "C28") (pin "1") (pinfunction "1_1") (pintype "passive"))
      (node (ref "R50") (pin "2") (pinfunction "2_2") (pintype "passive"))
      (node (ref "R56") (pin "2") (pinfunction "2_2") (pintype "passive"))
      (node (ref "R57") (pin "2") (pinfunction "2_2") (pintype "passive"))
      (node (ref "R58") (pin "2") (pinfunction "2_2") (pintype "passive"))
      (node (ref "R59") (pin "2") (pinfunction "2_2") (pintype "passive"))
      (node (ref "R60") (pin "2") (pinfunction "2_2") (pintype "passive"))
    )
    (net (code "12") (name "Net-(C28-Pad2)") (class "Default")
      (node (ref "C28") (pin "2") (pinfunction "2_2") (pintype "passive"))
      (node (ref "R61") (pin "1") (pinfunction "1_1") (pintype "passive"))
    )
    (net (code "13") (name "Net-(C29-Pad2)") (class "Default")
      (node (ref "C29") (pin "2") (pinfunction "2_2") (pintype "passive"))
      (node (ref "C30") (pin "1") (pinfunction "1_1") (pintype "passive"))
      (node (ref "R63") (pin "2") (pinfunction "2_2") (pintype "passive"))
    )
    (net (code "14") (name "Net-(D1-A)") (class "Default")
      (node (ref "C4") (pin "1") (pinfunction "1_1") (pintype "passive"))
      (node (ref "C6") (pin "1") (pinfunction "1_1") (pintype "passive"))
      (node (ref "D1") (pin "2") (pinfunction "A_2") (pintype "passive"))
      (node (ref "R26") (pin "2") (pinfunction "2_2") (pintype "passive"))
    )
    (net (code "15") (name "Net-(D1-C)") (class "Default")
      (node (ref "C3") (pin "1") (pinfunction "1_1") (pintype "passive"))
      (node (ref "D1") (pin "1") (pinfunction "C_1") (pintype "passive"))
      (node (ref "T11") (pin "3") (pinfunction "C_3") (pintype "passive"))
    )
    (net (code "16") (name "Net-(D2-A)") (class "Default")
      (node (ref "C13") (pin "1") (pinfunction "1_1") (pintype "passive"))
      (node (ref "C14") (pin "1") (pinfunction "1_1") (pintype "passive"))
      (node (ref "D2") (pin "2") (pinfunction "A_2") (pintype "passive"))
      (node (ref "R23") (pin "2") (pinfunction "2_2") (pintype "passive"))
    )
    (net (code "17") (name "Net-(D2-C)") (class "Default")
      (node (ref "C12") (pin "1") (pinfunction "1_1") (pintype "passive"))
      (node (ref "D2") (pin "1") (pinfunction "C_1") (pintype "passive"))
      (node (ref "T13") (pin "3") (pinfunction "C_3") (pintype "passive"))
    )
    (net (code "18") (name "Net-(IC1A-+IN)") (class "Default")
      (node (ref "IC1") (pin "3") (pinfunction "+IN_3") (pintype "input"))
      (node (ref "R34") (pin "2") (pinfunction "2_2") (pintype "passive"))
    )
    (net (code "19") (name "Net-(IC1A--IN)") (class "Default")
      (node (ref "C10") (pin "-") (pinfunction "-_-") (pintype "passive"))
      (node (ref "C9") (pin "1") (pinfunction "1_1") (pintype "passive"))
      (node (ref "IC1") (pin "2") (pinfunction "-IN_2") (pintype "input"))
      (node (ref "R33") (pin "2") (pinfunction "2_2") (pintype "passive"))
      (node (ref "R35") (pin "1") (pinfunction "1_1") (pintype "passive"))
    )
    (net (code "20") (name "Net-(IC1A-OUT)") (class "Default")
      (node (ref "C9") (pin "2") (pinfunction "2_2") (pintype "passive"))
      (node (ref "IC1") (pin "1") (pinfunction "OUT_1") (pintype "output"))
      (node (ref "R35") (pin "2") (pinfunction "2_2") (pintype "passive"))
      (node (ref "R36") (pin "P$1") (pinfunction "A_P$1") (pintype "passive"))
      (node (ref "R36") (pin "P$2") (pinfunction "S_P$2") (pintype "passive"))
      (node (ref "R37") (pin "1") (pinfunction "1_1") (pintype "passive"))
    )
    (net (code "21") (name "Net-(IC1B-+IN)") (class "Default")
      (node (ref "IC1") (pin "5") (pinfunction "+IN_5") (pintype "input"))
      (node (ref "R45") (pin "2") (pinfunction "2_2") (pintype "passive"))
    )
    (net (code "22") (name "Net-(IC1B--IN)") (class "Default")
      (node (ref "C17") (pin "1") (pinfunction "1_1") (pintype "passive"))
      (node (ref "C18") (pin "-") (pinfunction "-_-") (pintype "passive"))
      (node (ref "IC1") (pin "6") (pinfunction "-IN_6") (pintype "input"))
      (node (ref "R44") (pin "2") (pinfunction "2_2") (pintype "passive"))
      (node (ref "R46") (pin "1") (pinfunction "1_1") (pintype "passive"))
    )
    (net (code "23") (name "Net-(IC1B-OUT)") (class "Default")
      (node (ref "C17") (pin "2") (pinfunction "2_2") (pintype "passive"))
      (node (ref "IC1") (pin "7") (pinfunction "OUT_7") (pintype "output"))
      (node (ref "R46") (pin "2") (pinfunction "2_2") (pintype "passive"))
      (node (ref "R47") (pin "P$1") (pinfunction "A_P$1") (pintype "passive"))
      (node (ref "R47") (pin "P$2") (pinfunction "S_P$2") (pintype "passive"))
      (node (ref "R48") (pin "1") (pinfunction "1_1") (pintype "passive"))
    )
    (net (code "24") (name "Net-(IC2A-I)") (class "Default")
      (node (ref "C22") (pin "2") (pinfunction "2_2") (pintype "passive"))
      (node (ref "IC2") (pin "1") (pinfunction "I_1") (pintype "input"))
      (node (ref "R49") (pin "1") (pinfunction "1_1") (pintype "passive"))
    )
    (net (code "25") (name "Net-(IC2A-O)") (class "Default")
      (node (ref "IC2") (pin "2") (pinfunction "O_2") (pintype "output"))
      (node (ref "R49") (pin "2") (pinfunction "2_2") (pintype "passive"))
      (node (ref "R50") (pin "1") (pinfunction "1_1") (pintype "passive"))
    )
    (net (code "26") (name "Net-(IC2B-I)") (class "Default")
      (node (ref "C23") (pin "2") (pinfunction "2_2") (pintype "passive"))
      (node (ref "IC2") (pin "3") (pinfunction "I_3") (pintype "input"))
      (node (ref "R51") (pin "1") (pinfunction "1_1") (pintype "passive"))
    )
    (net (code "27") (name "Net-(IC2B-O)") (class "Default")
      (node (ref "IC2") (pin "4") (pinfunction "O_4") (pintype "output"))
      (node (ref "R51") (pin "2") (pinfunction "2_2") (pintype "passive"))
      (node (ref "R56") (pin "1") (pinfunction "1_1") (pintype "passive"))
    )
    (net (code "28") (name "Net-(IC2C-I)") (class "Default")
      (node (ref "C24") (pin "2") (pinfunction "2_2") (pintype "passive"))
      (node (ref "IC2") (pin "5") (pinfunction "I_5") (pintype "input"))
      (node (ref "R52") (pin "1") (pinfunction "1_1") (pintype "passive"))
    )
    (net (code "29") (name "Net-(IC2C-O)") (class "Default")
      (node (ref "IC2") (pin "6") (pinfunction "O_6") (pintype "output"))
      (node (ref "R52") (pin "2") (pinfunction "2_2") (pintype "passive"))
      (node (ref "R57") (pin "1") (pinfunction "1_1") (pintype "passive"))
    )
    (net (code "30") (name "Net-(IC2D-I)") (class "Default")
      (node (ref "C25") (pin "2") (pinfunction "2_2") (pintype "passive"))
      (node (ref "IC2") (pin "9") (pinfunction "I_9") (pintype "input"))
      (node (ref "R53") (pin "1") (pinfunction "1_1") (pintype "passive"))
    )
    (net (code "31") (name "Net-(IC2D-O)") (class "Default")
      (node (ref "IC2") (pin "8") (pinfunction "O_8") (pintype "output"))
      (node (ref "R53") (pin "2") (pinfunction "2_2") (pintype "passive"))
      (node (ref "R58") (pin "1") (pinfunction "1_1") (pintype "passive"))
    )
    (net (code "32") (name "Net-(IC2E-I)") (class "Default")
      (node (ref "C26") (pin "2") (pinfunction "2_2") (pintype "passive"))
      (node (ref "IC2") (pin "11") (pinfunction "I_11") (pintype "input"))
      (node (ref "R54") (pin "1") (pinfunction "1_1") (pintype "passive"))
    )
    (net (code "33") (name "Net-(IC2E-O)") (class "Default")
      (node (ref "IC2") (pin "10") (pinfunction "O_10") (pintype "output"))
      (node (ref "R54") (pin "2") (pinfunction "2_2") (pintype "passive"))
      (node (ref "R59") (pin "1") (pinfunction "1_1") (pintype "passive"))
    )
    (net (code "34") (name "Net-(IC2F-I)") (class "Default")
      (node (ref "C27") (pin "2") (pinfunction "2_2") (pintype "passive"))
      (node (ref "IC2") (pin "13") (pinfunction "I_13") (pintype "input"))
      (node (ref "R55") (pin "1") (pinfunction "1_1") (pintype "passive"))
    )
    (net (code "35") (name "Net-(IC2F-O)") (class "Default")
      (node (ref "IC2") (pin "12") (pinfunction "O_12") (pintype "output"))
      (node (ref "R55") (pin "2") (pinfunction "2_2") (pintype "passive"))
      (node (ref "R60") (pin "1") (pinfunction "1_1") (pintype "passive"))
    )
    (net (code "36") (name "Net-(IC3A--IN)") (class "Default")
      (node (ref "C29") (pin "1") (pinfunction "1_1") (pintype "passive"))
      (node (ref "IC3") (pin "2") (pinfunction "-IN_2") (pintype "input"))
      (node (ref "R61") (pin "2") (pinfunction "2_2") (pintype "passive"))
      (node (ref "R62") (pin "1") (pinfunction "1_1") (pintype "passive"))
    )
    (net (code "37") (name "Net-(IC3B--IN)") (class "Default")
      (node (ref "IC3") (pin "6") (pinfunction "-IN_6") (pintype "input"))
      (node (ref "IC3") (pin "7") (pinfunction "OUT_7") (pintype "output"))
    )
    (net (code "38") (name "Net-(IC4-BP)") (class "Default")
      (node (ref "C32") (pin "1") (pinfunction "1_1") (pintype "passive"))
      (node (ref "IC4") (pin "4") (pinfunction "BP_4") (pintype "input"))
    )
    (net (code "39") (name "Net-(J1-LEFT)") (class "Default")
      (node (ref "J1") (pin "2") (pinfunction "LEFT_2") (pintype "bidirectional"))
      (node (ref "R37") (pin "2") (pinfunction "2_2") (pintype "passive"))
    )
    (net (code "40") (name "Net-(J1-RIGHT)") (class "Default")
      (node (ref "J1") (pin "3") (pinfunction "RIGHT_3") (pintype "bidirectional"))
      (node (ref "R48") (pin "2") (pinfunction "2_2") (pintype "passive"))
    )
    (net (code "41") (name "Net-(R1-Pad1)") (class "Default")
      (node (ref "R1") (pin "1") (pinfunction "1_1") (pintype "passive"))
      (node (ref "R4") (pin "2") (pinfunction "2_2") (pintype "passive"))
      (node (ref "T2") (pin "B") (pinfunction "B_B") (pintype "passive"))
    )
    (net (code "42") (name "Net-(R1-Pad2)") (class "Default")
      (node (ref "R1") (pin "2") (pinfunction "2_2") (pintype "passive"))
      (node (ref "R9") (pin "2") (pinfunction "2_2") (pintype "passive"))
      (node (ref "S1") (pin "3") (pinfunction "3_3") (pintype "passive"))
      (node (ref "T2") (pin "E") (pinfunction "E_E") (pintype "passive"))
      (node (ref "T4") (pin "E") (pinfunction "E_E") (pintype "passive"))
    )
    (net (code "43") (name "Net-(R3-Pad2)") (class "Default")
      (node (ref "R3") (pin "2") (pinfunction "2_2") (pintype "passive"))
      (node (ref "S2") (pin "3") (pinfunction "3_3") (pintype "passive"))
    )
    (net (code "44") (name "Net-(R6-Pad2)") (class "Default")
      (node (ref "R6") (pin "2") (pinfunction "2_2") (pintype "passive"))
      (node (ref "S3") (pin "3") (pinfunction "3_3") (pintype "passive"))
    )
    (net (code "45") (name "Net-(R8-Pad2)") (class "Default")
      (node (ref "R8") (pin "2") (pinfunction "2_2") (pintype "passive"))
      (node (ref "R9") (pin "1") (pinfunction "1_1") (pintype "passive"))
      (node (ref "T4") (pin "B") (pinfunction "B_B") (pintype "passive"))
    )
    (net (code "46") (name "Net-(R10-Pad2)") (class "Default")
      (node (ref "R10") (pin "2") (pinfunction "2_2") (pintype "passive"))
      (node (ref "R12") (pin "2") (pinfunction "2_2") (pintype "passive"))
      (node (ref "T4") (pin "C") (pinfunction "C_C") (pintype "passive"))
    )
    (net (code "47") (name "Net-(R21-Pad1)") (class "Default")
      (node (ref "R21") (pin "1") (pinfunction "1_1") (pintype "passive"))
      (node (ref "R5") (pin "2") (pinfunction "2_2") (pintype "passive"))
      (node (ref "T2") (pin "C") (pinfunction "C_C") (pintype "passive"))
    )
    (net (code "48") (name "Net-(R25-A)") (class "Default")
      (node (ref "R16") (pin "2") (pinfunction "2_2") (pintype "passive"))
      (node (ref "R25") (pin "P$1") (pinfunction "A_P$1") (pintype "passive"))
      (node (ref "R25") (pin "P$2") (pinfunction "S_P$2") (pintype "passive"))
    )
    (net (code "49") (name "Net-(R27-Pad1)") (class "Default")
      (node (ref "R27") (pin "1") (pinfunction "1_1") (pintype "passive"))
      (node (ref "R28") (pin "2") (pinfunction "2_2") (pintype "passive"))
    )
    (net (code "50") (name "Net-(R36-E)") (class "Default")
      (node (ref "C10") (pin "+") (pinfunction "+_+") (pintype "passive"))
      (node (ref "R36") (pin "P$3") (pinfunction "E_P$3") (pintype "passive"))
    )
    (net (code "51") (name "Net-(R38-Pad2)") (class "Default")
      (node (ref "R38") (pin "2") (pinfunction "2_2") (pintype "passive"))
      (node (ref "R39") (pin "1") (pinfunction "1_1") (pintype "passive"))
    )
    (net (code "52") (name "Net-(R47-E)") (class "Default")
      (node (ref "C18") (pin "+") (pinfunction "+_+") (pintype "passive"))
      (node (ref "R47") (pin "P$3") (pinfunction "E_P$3") (pintype "passive"))
    )
    (net (code "53") (name "Net-(T1-B)") (class "Default")
      (node (ref "R2") (pin "2") (pinfunction "2_2") (pintype "passive"))
      (node (ref "R3") (pin "1") (pinfunction "1_1") (pintype "passive"))
      (node (ref "T1") (pin "1") (pinfunction "B_1") (pintype "passive"))
    )
    (net (code "54") (name "Net-(T1-C)") (class "Default")
      (node (ref "R4") (pin "1") (pinfunction "1_1") (pintype "passive"))
      (node (ref "T1") (pin "3") (pinfunction "C_3") (pintype "passive"))
    )
    (net (code "55") (name "Net-(T3-B)") (class "Default")
      (node (ref "R6") (pin "1") (pinfunction "1_1") (pintype "passive"))
      (node (ref "R7") (pin "2") (pinfunction "2_2") (pintype "passive"))
      (node (ref "T3") (pin "1") (pinfunction "B_1") (pintype "passive"))
    )
    (net (code "56") (name "Net-(T3-C)") (class "Default")
      (node (ref "R8") (pin "1") (pinfunction "1_1") (pintype "passive"))
      (node (ref "T3") (pin "3") (pinfunction "C_3") (pintype "passive"))
    )
    (net (code "57") (name "Net-(T5-B)") (class "Default")
      (node (ref "R12") (pin "1") (pinfunction "1_1") (pintype "passive"))
      (node (ref "T5") (pin "1") (pinfunction "B_1") (pintype "passive"))
    )
    (net (code "58") (name "Net-(T5-C)") (class "Default")
      (node (ref "R13") (pin "1") (pinfunction "1_1") (pintype "passive"))
      (node (ref "T5") (pin "3") (pinfunction "C_3") (pintype "passive"))
    )
    (net (code "59") (name "Net-(T5-E)") (class "Default")
      (node (ref "C1") (pin "+") (pinfunction "+_+") (pintype "passive"))
      (node (ref "R15") (pin "2") (pinfunction "2_2") (pintype "passive"))
      (node (ref "R18") (pin "2") (pinfunction "2_2") (pintype "passive"))
      (node (ref "R19") (pin "1") (pinfunction "1_1") (pintype "passive"))
      (node (ref "T5") (pin "2") (pinfunction "E_2") (pintype "passive"))
    )
    (net (code "60") (name "Net-(T6-B)") (class "Default")
      (node (ref "R10") (pin "1") (pinfunction "1_1") (pintype "passive"))
      (node (ref "R11") (pin "2") (pinfunction "2_2") (pintype "passive"))
      (node (ref "T6") (pin "1") (pinfunction "B_1") (pintype "passive"))
    )
    (net (code "61") (name "Net-(T6-C)") (class "Default")
      (node (ref "C33") (pin "+") (pinfunction "+_+") (pintype "passive"))
      (node (ref "R16") (pin "1") (pinfunction "1_1") (pintype "passive"))
      (node (ref "R17") (pin "2") (pinfunction "2_2") (pintype "passive"))
      (node (ref "T6") (pin "3") (pinfunction "C_3") (pintype "passive"))
    )
    (net (code "62") (name "Net-(T7-B)") (class "Default")
      (node (ref "R17") (pin "1") (pinfunction "1_1") (pintype "passive"))
      (node (ref "T7") (pin "1") (pinfunction "B_1") (pintype "passive"))
    )
    (net (code "63") (name "Net-(T7-C)") (class "Default")
      (node (ref "R15") (pin "1") (pinfunction "1_1") (pintype "passive"))
      (node (ref "T7") (pin "3") (pinfunction "C_3") (pintype "passive"))
      (node (ref "T8") (pin "3") (pinfunction "C_3") (pintype "passive"))
    )
    (net (code "64") (name "Net-(T8-B)") (class "Default")
      (node (ref "R22") (pin "1") (pinfunction "1_1") (pintype "passive"))
      (node (ref "T8") (pin "1") (pinfunction "B_1") (pintype "passive"))
    )
    (net (code "65") (name "Net-(T9-B)") (class "Default")
      (node (ref "R19") (pin "2") (pinfunction "2_2") (pintype "passive"))
      (node (ref "T9") (pin "1") (pinfunction "B_1") (pintype "passive"))
    )
    (net (code "66") (name "Net-(T9-E)") (class "Default")
      (node (ref "R20") (pin "2") (pinfunction "2_2") (pintype "passive"))
      (node (ref "R26") (pin "1") (pinfunction "1_1") (pintype "passive"))
      (node (ref "T9") (pin "2") (pinfunction "E_2") (pintype "passive"))
    )
    (net (code "67") (name "Net-(T10-B)") (class "Default")
      (node (ref "R21") (pin "2") (pinfunction "2_2") (pintype "passive"))
      (node (ref "T10") (pin "1") (pinfunction "B_1") (pintype "passive"))
    )
    (net (code "68") (name "Net-(T10-C)") (class "Default")
      (node (ref "R14") (pin "1") (pinfunction "1_1") (pintype "passive"))
      (node (ref "T10") (pin "3") (pinfunction "C_3") (pintype "passive"))
    )
    (net (code "69") (name "Net-(T10-E)") (class "Default")
      (node (ref "C19") (pin "+") (pinfunction "+_+") (pintype "passive"))
      (node (ref "R22") (pin "2") (pinfunction "2_2") (pintype "passive"))
      (node (ref "R23") (pin "1") (pinfunction "1_1") (pintype "passive"))
      (node (ref "T10") (pin "2") (pinfunction "E_2") (pintype "passive"))
    )
    (net (code "70") (name "Net-(T11-B)") (class "Default")
      (node (ref "C5") (pin "1") (pinfunction "1_1") (pintype "passive"))
      (node (ref "R28") (pin "1") (pinfunction "1_1") (pintype "passive"))
      (node (ref "T11") (pin "1") (pinfunction "B_1") (pintype "passive"))
    )
    (net (code "71") (name "Net-(T11-E)") (class "Default")
      (node (ref "R29") (pin "2") (pinfunction "2_2") (pintype "passive"))
      (node (ref "T11") (pin "2") (pinfunction "E_2") (pintype "passive"))
    )
    (net (code "72") (name "Net-(T12-B)") (class "Default")
      (node (ref "C7") (pin "2") (pinfunction "2_2") (pintype "passive"))
      (node (ref "R31") (pin "2") (pinfunction "2_2") (pintype "passive"))
      (node (ref "T12") (pin "1") (pinfunction "B_1") (pintype "passive"))
    )
    (net (code "73") (name "Net-(T12-E)") (class "Default")
      (node (ref "C8") (pin "1") (pinfunction "1_1") (pintype "passive"))
      (node (ref "R30") (pin "1") (pinfunction "1_1") (pintype "passive"))
      (node (ref "R32") (pin "2") (pinfunction "2_2") (pintype "passive"))
      (node (ref "T12") (pin "2") (pinfunction "E_2") (pintype "passive"))
    )
    (net (code "74") (name "Net-(T13-B)") (class "Default")
      (node (ref "C11") (pin "1") (pinfunction "1_1") (pintype "passive"))
      (node (ref "R38") (pin "1") (pinfunction "1_1") (pintype "passive"))
      (node (ref "T13") (pin "1") (pinfunction "B_1") (pintype "passive"))
    )
    (net (code "75") (name "Net-(T13-E)") (class "Default")
      (node (ref "R40") (pin "2") (pinfunction "2_2") (pintype "passive"))
      (node (ref "T13") (pin "2") (pinfunction "E_2") (pintype "passive"))
    )
    (net (code "76") (name "Net-(T14-B)") (class "Default")
      (node (ref "C15") (pin "2") (pinfunction "2_2") (pintype "passive"))
      (node (ref "R42") (pin "2") (pinfunction "2_2") (pintype "passive"))
      (node (ref "T14") (pin "1") (pinfunction "B_1") (pintype "passive"))
    )
    (net (code "77") (name "Net-(T14-E)") (class "Default")
      (node (ref "C16") (pin "1") (pinfunction "1_1") (pintype "passive"))
      (node (ref "R41") (pin "1") (pinfunction "1_1") (pintype "passive"))
      (node (ref "R43") (pin "2") (pinfunction "2_2") (pintype "passive"))
      (node (ref "T14") (pin "2") (pinfunction "E_2") (pintype "passive"))
    )
    (net (code "78") (name "unconnected-(S1-Pad2)") (class "Default")
      (node (ref "S1") (pin "2") (pinfunction "2_2") (pintype "passive"))
    )
    (net (code "79") (name "unconnected-(S1-Pad4)") (class "Default")
      (node (ref "S1") (pin "4") (pinfunction "4_4") (pintype "passive"))
    )
    (net (code "80") (name "unconnected-(S2-Pad2)") (class "Default")
      (node (ref "S2") (pin "2") (pinfunction "2_2") (pintype "passive"))
    )
    (net (code "81") (name "unconnected-(S2-Pad4)") (class "Default")
      (node (ref "S2") (pin "4") (pinfunction "4_4") (pintype "passive"))
    )
    (net (code "82") (name "unconnected-(S3-Pad2)") (class "Default")
      (node (ref "S3") (pin "2") (pinfunction "2_2") (pintype "passive"))
    )
    (net (code "83") (name "unconnected-(S3-Pad4)") (class "Default")
      (node (ref "S3") (pin "4") (pinfunction "4_4") (pintype "passive"))
    )
  )
)
